# Pg06__SysBoot_LEDS_Mech.net
KiCad netlist of a schematic drawn in Altium Designer
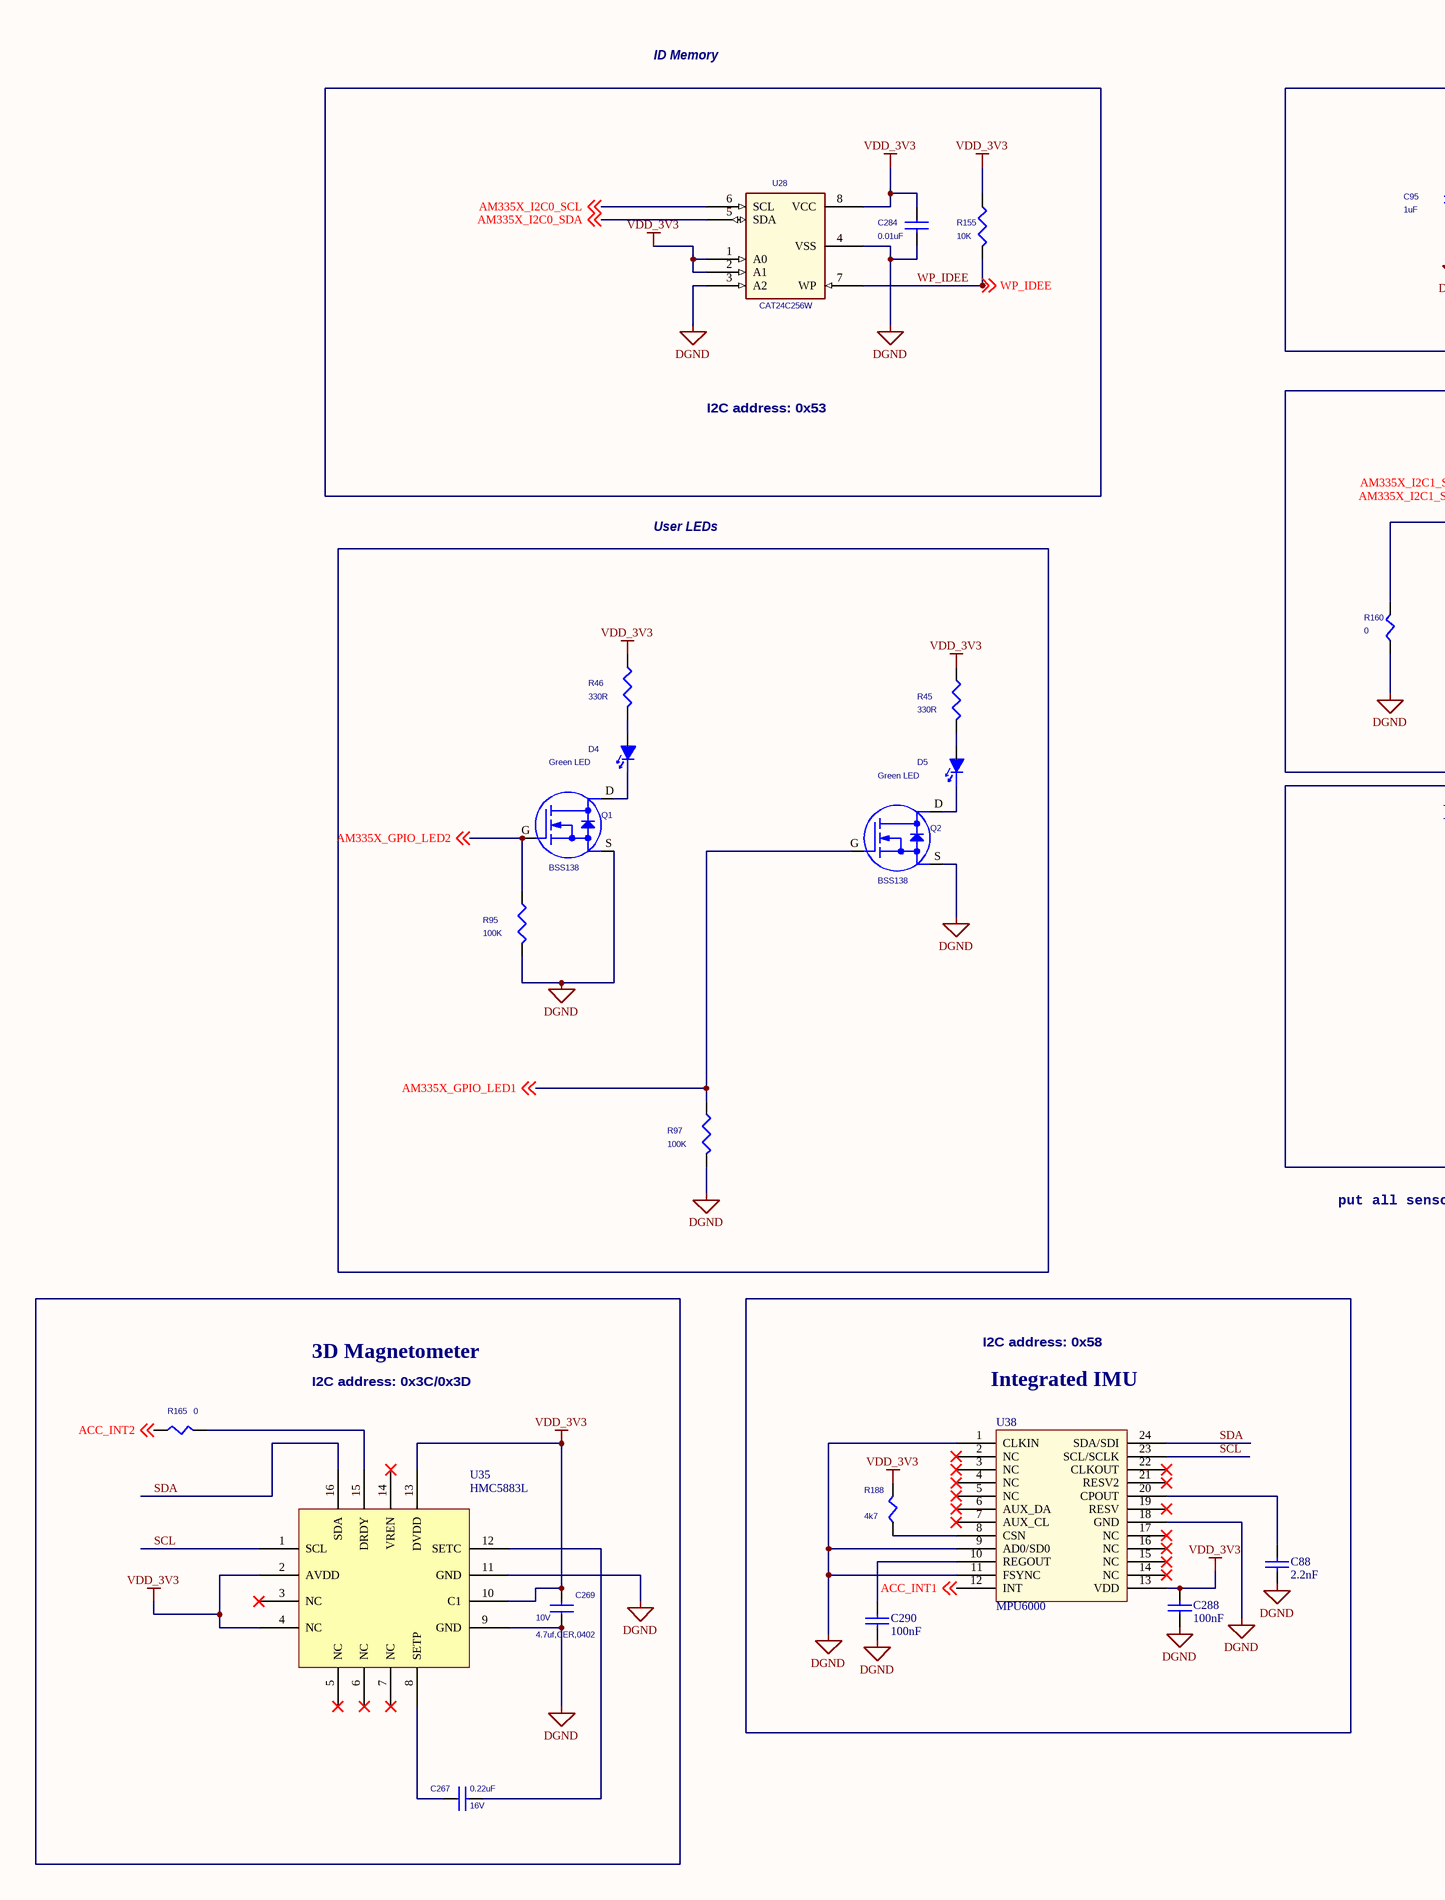
[diagram p0: Pg06_ SysBoot_LEDS_Mech.SchDoc, left]
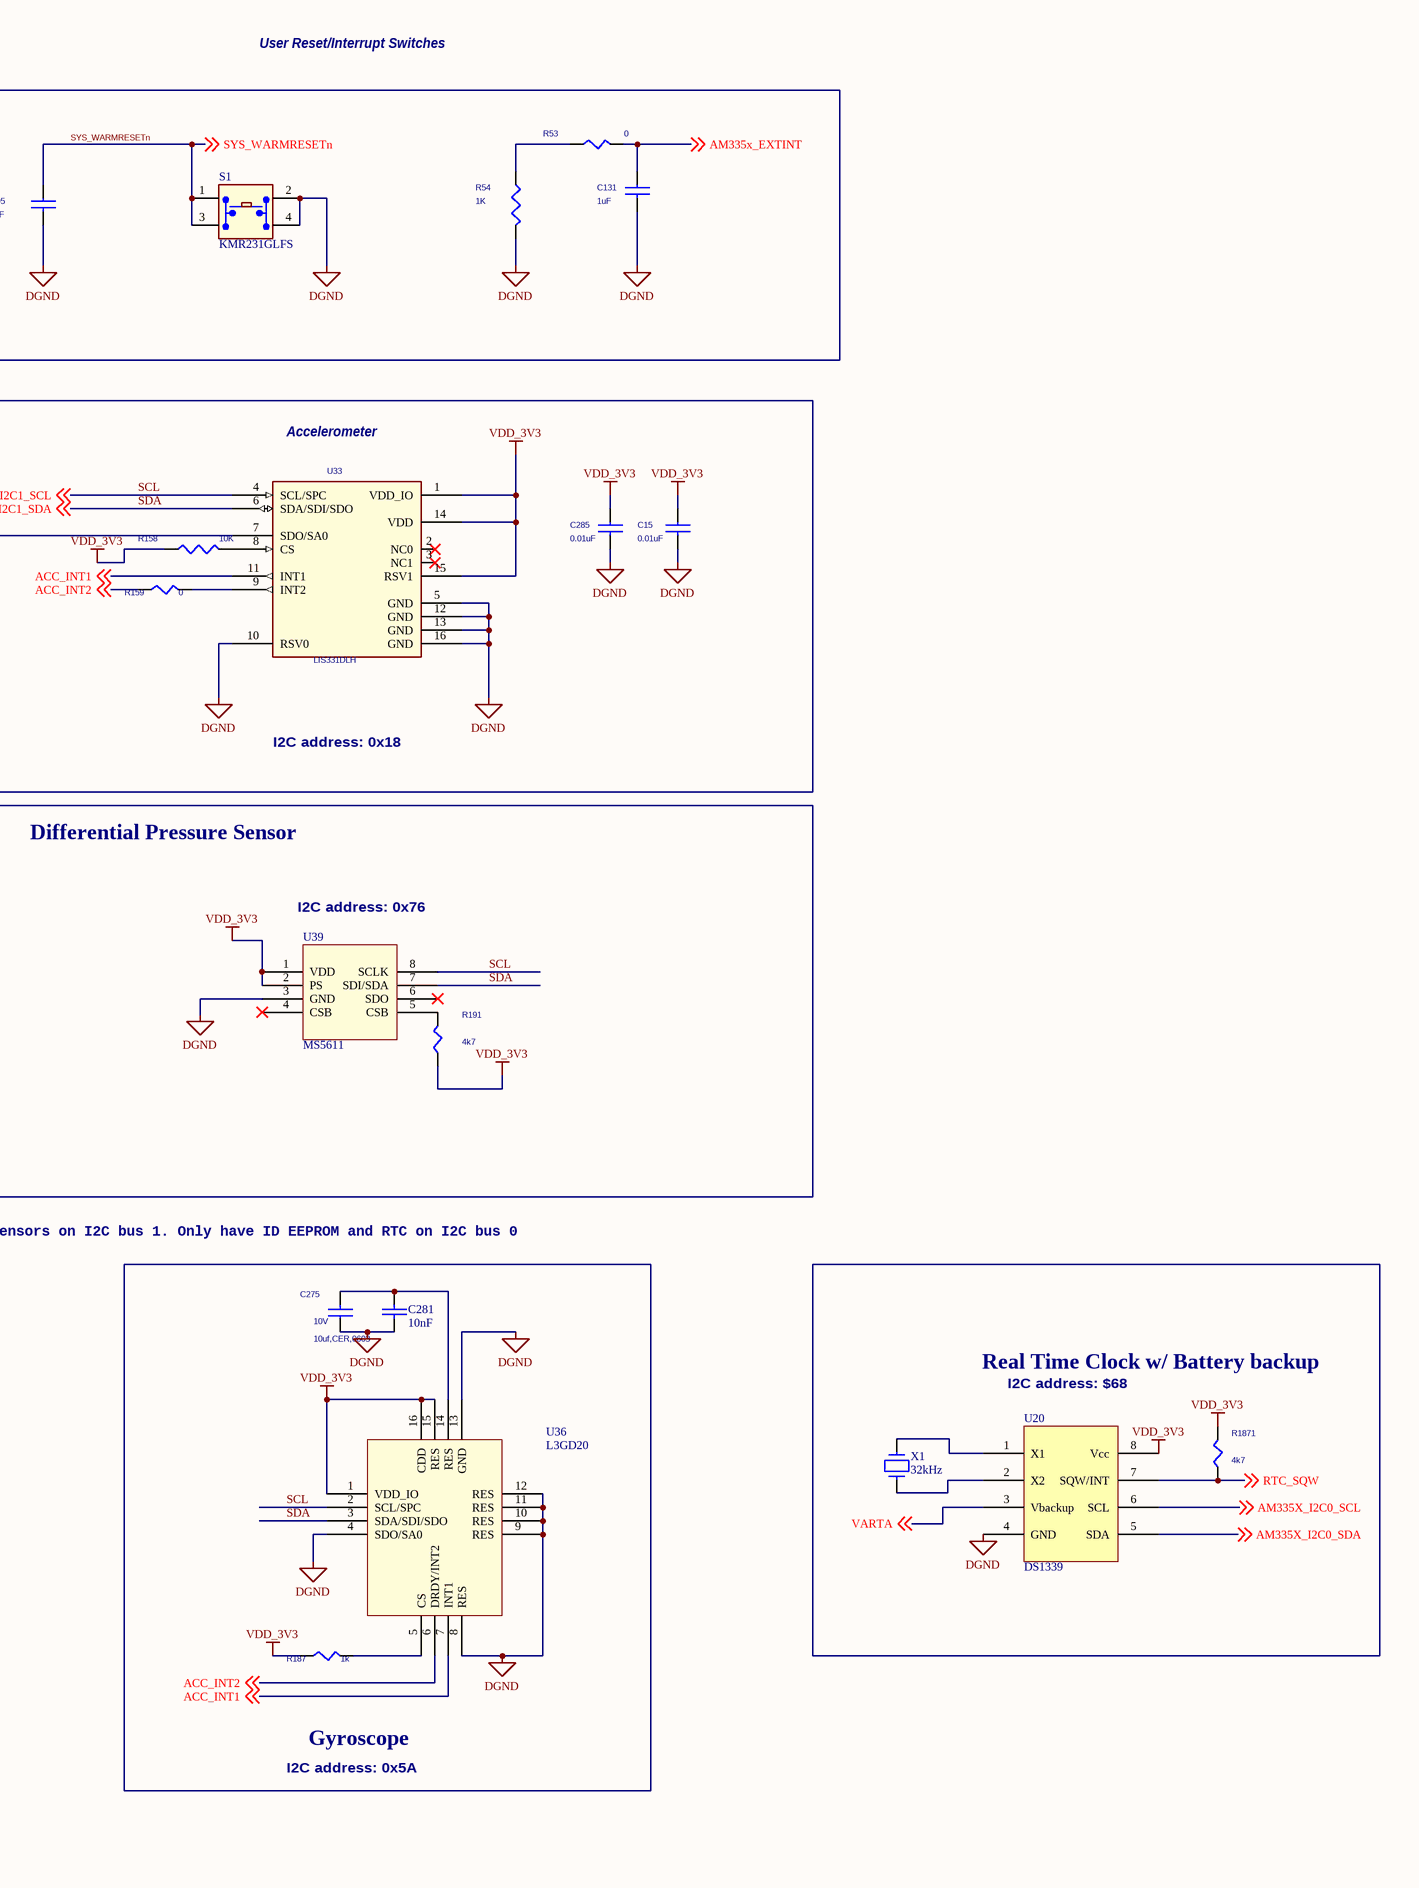
[diagram p1: Pg06_ SysBoot_LEDS_Mech.SchDoc, right]

(export (version "E")
  (design (tool "Eeschema 10.0.6"))
  (components
    (comp (ref "C15")
      (value "0.01uF")
      (footprint "SM-7351-CAP-0402")
      (fields (field (name "MFR") "Panasonic") (field (name "TIINTPARTNUMBER") "1C0012"))
      (libsource (lib "*") (part "0.01uFCapacitor16V10%0402_Dup1"))
    )
    (comp (ref "C88")
      (value "2.2nF")
      (footprint "0603")
      (description "Ceramic capacitor")
      (libsource (lib "CCDHeadBoard") (part "CAP_CER"))
    )
    (comp (ref "C95")
      (value "1uF")
      (footprint "SM-7351-CAP-0402")
      (fields (field (name "MFR") "AVX") (field (name "TIINTPARTNUMBER") "1C0084"))
      (libsource (lib "*") (part "1uFCapacitor10V10%0402_Dup1"))
    )
    (comp (ref "C131")
      (value "1uF")
      (footprint "SM-7351-CAP-0402")
      (fields (field (name "MFR") "AVX") (field (name "TIINTPARTNUMBER") "1C0084"))
      (libsource (lib "*") (part "1uFCapacitor10V10%0402_Dup1"))
    )
    (comp (ref "C267")
      (value "0.22uF")
      (footprint "sc0402")
      (fields (field (name "VOLTAGE") "16V"))
      (libsource (lib "*") (part "0402_0r01uf_x7r_16v_10"))
    )
    (comp (ref "C269")
      (value "4.7uf,CER,0402")
      (footprint "sc0402")
      (fields (field (name "VOLTAGE") "10V"))
      (libsource (lib "*") (part "cap_0402_0r1uf_x7r_10v"))
    )
    (comp (ref "C275")
      (value "10uf,CER,0603")
      (footprint "0603")
      (fields (field (name "VOLTAGE") "10V"))
      (libsource (lib "*") (part "cap_0402_0r1uf_x7r_10v"))
    )
    (comp (ref "C281")
      (value "10nF")
      (footprint "SM-7351-CAP-0402")
      (description "Ceramic capacitor")
      (libsource (lib "CCDHeadBoard") (part "CAP_CER"))
    )
    (comp (ref "C284")
      (value "0.01uF")
      (footprint "SM-7351-CAP-0402")
      (fields (field (name "MFR") "Panasonic") (field (name "TIINTPARTNUMBER") "1C0012"))
      (libsource (lib "*") (part "0.01uFCapacitor16V10%0402_Dup1"))
    )
    (comp (ref "C285")
      (value "0.01uF")
      (footprint "SM-7351-CAP-0402")
      (fields (field (name "MFR") "Panasonic") (field (name "TIINTPARTNUMBER") "1C0012"))
      (libsource (lib "*") (part "0.01uFCapacitor16V10%0402_Dup1"))
    )
    (comp (ref "C288")
      (value "100nF")
      (footprint "0603")
      (description "Ceramic capacitor")
      (libsource (lib "CCDHeadBoard") (part "CAP_CER"))
    )
    (comp (ref "C290")
      (value "100nF")
      (footprint "0603")
      (description "Ceramic capacitor")
      (libsource (lib "CCDHeadBoard") (part "CAP_CER"))
    )
    (comp (ref "D4")
      (value "Green LED")
      (footprint "sm_led_0805")
      (fields (field (name "TIINTPARTNUMBER") "1F0008") (field (name "MFR") "Dialight"))
      (libsource (lib "*") (part "LED_Green"))
    )
    (comp (ref "D5")
      (value "Green LED")
      (footprint "sm_led_0805")
      (fields (field (name "TIINTPARTNUMBER") "1F0008") (field (name "MFR") "Dialight"))
      (libsource (lib "*") (part "LED_Green"))
    )
    (comp (ref "Q1")
      (value "BSS138")
      (footprint "SOT23-3")
      (description "MOSFET Nchan 50V 200mA")
      (fields (field (name "TIINTPARTNUMBER") "1Q0019") (field (name "MFR") "Diodes Inc."))
      (libsource (lib "*") (part "MOSFET_NChan_BSS138_Dup1"))
    )
    (comp (ref "Q2")
      (value "BSS138")
      (footprint "SOT23-3")
      (description "MOSFET Nchan 50V 200mA")
      (fields (field (name "TIINTPARTNUMBER") "1Q0019") (field (name "MFR") "Diodes Inc."))
      (libsource (lib "*") (part "MOSFET_NChan_BSS138_Dup1"))
    )
    (comp (ref "R45")
      (value "330R")
      (footprint "SM-7351-RES-0402")
      (description "Resistor 150ohm 1/16W 5% 0402")
      (fields (field (name "MFR") "Stackpole Electronics") (field (name "TIINTPARTNUMBER") "1R0179"))
      (libsource (lib "*") (part "150ohm1/16W1%SMD0402"))
    )
    (comp (ref "R46")
      (value "330R")
      (footprint "SM-7351-RES-0402")
      (description "Resistor 150ohm 1/16W 5% 0402")
      (fields (field (name "MFR") "Stackpole Electronics") (field (name "TIINTPARTNUMBER") "1R0179"))
      (libsource (lib "*") (part "150ohm1/16W1%SMD0402"))
    )
    (comp (ref "R53")
      (value "0")
      (footprint "SM-7351-RES-0402")
      (description "Resistor Zero ohm Jumper 0402")
      (fields (field (name "TIINTPARTNUMBER") "1R0098") (field (name "MFR") "Panasonic"))
      (libsource (lib "*") (part "ZeroOhmResistor1/16W0402_Dup1"))
    )
    (comp (ref "R54")
      (value "1K")
      (footprint "SM-7351-RES-0402")
      (description "Resistor 1Kohm 1/16W 5% 0402")
      (fields (field (name "MFR") "Panasonic") (field (name "TIINTPARTNUMBER") "1R0027"))
      (libsource (lib "*") (part "1KOhmResistor1/16W0402_Dup1"))
    )
    (comp (ref "R95")
      (value "100K")
      (footprint "SM-7351-RES-0402")
      (fields (field (name "TIINTPARTNUMBER") "1R0181") (field (name "MFR") "Stackpole Electronics"))
      (libsource (lib "*") (part "100KOhmResistor1/16W0402_Dup1"))
    )
    (comp (ref "R97")
      (value "100K")
      (footprint "SM-7351-RES-0402")
      (fields (field (name "TIINTPARTNUMBER") "1R0181") (field (name "MFR") "Stackpole Electronics"))
      (libsource (lib "*") (part "100KOhmResistor1/16W0402_Dup1"))
    )
    (comp (ref "R155")
      (value "10K")
      (footprint "SM-7351-RES-0402")
      (description "Resistor 10Kohm 1/16W 5% 0402")
      (fields (field (name "TIINTPARTNUMBER") "1R0168") (field (name "MFR") "Rohm"))
      (libsource (lib "*") (part "10KOhmResistor1/16W0402_Dup1"))
    )
    (comp (ref "R158")
      (value "10K")
      (footprint "SM-7351-RES-0402")
      (description "Resistor 10Kohm 1/16W 5% 0402")
      (fields (field (name "TIINTPARTNUMBER") "1R0168") (field (name "MFR") "Rohm"))
      (libsource (lib "*") (part "10KOhmResistor1/16W0402_Dup1"))
    )
    (comp (ref "R159")
      (value "0")
      (footprint "SM-7351-RES-0402")
      (fields (field (name "MFR") "Panasonic") (field (name "TIINTPARTNUMBER") "1R0098"))
      (libsource (lib "*") (part "ZeroOhmResistor1/16W0402"))
    )
    (comp (ref "R160")
      (value "0")
      (footprint "SM-7351-RES-0402")
      (description "Resistor Zero ohm Jumper 0402")
      (fields (field (name "TIINTPARTNUMBER") "1R0098") (field (name "MFR") "Panasonic"))
      (libsource (lib "*") (part "ZeroOhmResistor1/16W0402_Dup4"))
    )
    (comp (ref "R165")
      (value "0")
      (footprint "SM-7351-RES-0402")
      (fields (field (name "MFR") "Panasonic") (field (name "TIINTPARTNUMBER") "1R0098"))
      (libsource (lib "*") (part "ZeroOhmResistor1/16W0402"))
    )
    (comp (ref "R187")
      (value "1k")
      (footprint "SM-7351-RES-0402")
      (fields (field (name "MFR") "Panasonic") (field (name "TIINTPARTNUMBER") "1R0098"))
      (libsource (lib "*") (part "ZeroOhmResistor1/16W0402"))
    )
    (comp (ref "R188")
      (value "4k7")
      (footprint "SM-7351-RES-0402")
      (fields (field (name "MFR") "Panasonic") (field (name "TIINTPARTNUMBER") "1R0098"))
      (libsource (lib "*") (part "ZeroOhmResistor1/16W0402"))
    )
    (comp (ref "R191")
      (value "4k7")
      (footprint "SM-7351-RES-0402")
      (fields (field (name "MFR") "Panasonic") (field (name "TIINTPARTNUMBER") "1R0098"))
      (libsource (lib "*") (part "ZeroOhmResistor1/16W0402"))
    )
    (comp (ref "R1871")
      (value "4k7")
      (footprint "SM-7351-RES-0402")
      (fields (field (name "MFR") "Panasonic") (field (name "TIINTPARTNUMBER") "1R0098"))
      (libsource (lib "*") (part "ZeroOhmResistor1/16W0402"))
    )
    (comp (ref "S1")
      (value "KMR231GLFS")
      (footprint "SW4SMD_63X161LS")
      (description "Microminiature Tact Switch for SMT")
      (fields (field (name "MANUFACTURER") "C&K Components"))
      (libsource (lib "BEAGLEBONEBLACK_REV A5B") (part "KMR2"))
    )
    (comp (ref "U20")
      (value "DS1339")
      (footprint "MSOP-MS8_N")
      (description "DS1339 RTC")
      (libsource (lib "Fireflash_B") (part "DS1339"))
    )
    (comp (ref "U28")
      (value "CAT24C256W")
      (footprint "SOIC_8")
      (description "EEPROM 256Kb I2C SOIC8")
      (fields (field (name "TIINTPARTNUMBER") "1A0225") (field (name "MFR") "On Semiconductor"))
      (libsource (lib "*") (part "CAT24C256W"))
    )
    (comp (ref "U33")
      (value "LIS331DLH")
      (footprint "LGA16pin_3x3")
      (description "Accelerometer 3 Axis I2C")
      (fields (field (name "MFR") "ST Microelectronics") (field (name "TIINTPARTNUMBER") "1A0227"))
      (libsource (lib "*") (part "LIS331DLH"))
    )
    (comp (ref "U35")
      (value "HMC5883L")
      (footprint "LPCC package")
      (description "3D Magnetometer")
      (libsource (lib "Fireflash_B") (part "HMC5883L"))
    )
    (comp (ref "U36")
      (value "L3GD20")
      (footprint "LCC 16pin 4x4mm 0.65mm pitch")
      (libsource (lib "testlib") (part "L3GD20"))
    )
    (comp (ref "U38")
      (value "MPU6000")
      (footprint "QFN_EPAD_24")
      (description "Invensemse 6-axis MPU")
      (libsource (lib "RedCape") (part "IMU6000"))
    )
    (comp (ref "U39")
      (value "MS5611")
      (footprint "MS5611-01BA03")
      (description "Pressure Sensor")
      (libsource (lib "RedCape") (part "MS5611"))
    )
    (comp (ref "X1")
      (value "32kHz")
      (footprint "Xtal 3215")
      (description "CRYSTAL")
      (libsource (lib "Fireflash_B") (part "CRYSTAL"))
    )
  )
  (nets
    (net (code "1") (name "ACC_INT1") (class "Default")
      (node (ref "U33") (pin "11") (pinfunction "INT1_11") (pintype "output"))
      (node (ref "U36") (pin "7") (pinfunction "INT1_7") (pintype "passive"))
      (node (ref "U38") (pin "12") (pinfunction "INT_12") (pintype "passive"))
    )
    (net (code "2") (name "ACC_INT2") (class "Default")
      (node (ref "R159") (pin "2") (pinfunction "P2_2") (pintype "passive"))
      (node (ref "R165") (pin "2") (pinfunction "P2_2") (pintype "passive"))
      (node (ref "U36") (pin "6") (pinfunction "DRDY/INT2_6") (pintype "passive"))
    )
    (net (code "3") (name "AM335X_GPIO_LED1") (class "Default")
      (node (ref "Q2") (pin "G") (pinfunction "GATE_G") (pintype "passive"))
      (node (ref "R97") (pin "2") (pinfunction "P2_2") (pintype "passive"))
    )
    (net (code "4") (name "AM335X_GPIO_LED2") (class "Default")
      (node (ref "Q1") (pin "G") (pinfunction "GATE_G") (pintype "passive"))
      (node (ref "R95") (pin "2") (pinfunction "P2_2") (pintype "passive"))
    )
    (net (code "5") (name "AM335X_I2C0_SCL") (class "Default")
      (node (ref "U20") (pin "6") (pinfunction "SCL_6") (pintype "passive"))
      (node (ref "U28") (pin "6") (pinfunction "SCL_6") (pintype "input"))
    )
    (net (code "6") (name "AM335X_I2C0_SDA") (class "Default")
      (node (ref "U20") (pin "5") (pinfunction "SDA_5") (pintype "passive"))
      (node (ref "U28") (pin "5") (pinfunction "SDA_5") (pintype "bidirectional"))
    )
    (net (code "7") (name "AM335X_I2C1_SCL") (class "Default")
      (node (ref "U33") (pin "4") (pinfunction "SCL/SPC_4") (pintype "input"))
      (node (ref "U35") (pin "1") (pinfunction "SCL_1") (pintype "passive"))
      (node (ref "U36") (pin "2") (pinfunction "SCL/SPC_2") (pintype "passive"))
      (node (ref "U38") (pin "23") (pinfunction "SCL/SCLK_23") (pintype "passive"))
      (node (ref "U39") (pin "8") (pinfunction "SCLK_8") (pintype "passive"))
    )
    (net (code "8") (name "AM335X_I2C1_SDA") (class "Default")
      (node (ref "U33") (pin "6") (pinfunction "SDA/SDI/SDO_6") (pintype "bidirectional"))
      (node (ref "U35") (pin "16") (pinfunction "SDA_16") (pintype "passive"))
      (node (ref "U36") (pin "3") (pinfunction "SDA/SDI/SDO_3") (pintype "passive"))
      (node (ref "U38") (pin "24") (pinfunction "SDA/SDI_24") (pintype "passive"))
      (node (ref "U39") (pin "7") (pinfunction "SDI/SDA_7") (pintype "passive"))
    )
    (net (code "9") (name "AM335x_EXTINT") (class "Default")
      (node (ref "C131") (pin "1") (pinfunction "1_1") (pintype "passive"))
      (node (ref "R53") (pin "1") (pinfunction "P1_1") (pintype "passive"))
    )
    (net (code "10") (name "DGND") (class "Default")
      (node (ref "C131") (pin "2") (pinfunction "2_2") (pintype "passive"))
      (node (ref "C15") (pin "2") (pinfunction "2_2") (pintype "passive"))
      (node (ref "C269") (pin "1") (pinfunction "1_1") (pintype "passive"))
      (node (ref "C275") (pin "1") (pinfunction "1_1") (pintype "passive"))
      (node (ref "C281") (pin "2") (pintype "passive"))
      (node (ref "C284") (pin "2") (pinfunction "2_2") (pintype "passive"))
      (node (ref "C285") (pin "2") (pinfunction "2_2") (pintype "passive"))
      (node (ref "C288") (pin "2") (pintype "passive"))
      (node (ref "C290") (pin "2") (pintype "passive"))
      (node (ref "C88") (pin "2") (pintype "passive"))
      (node (ref "C95") (pin "2") (pinfunction "2_2") (pintype "passive"))
      (node (ref "Q1") (pin "S") (pinfunction "SOURCE_S") (pintype "passive"))
      (node (ref "Q2") (pin "S") (pinfunction "SOURCE_S") (pintype "passive"))
      (node (ref "R160") (pin "2") (pinfunction "P2_2") (pintype "passive"))
      (node (ref "R54") (pin "1") (pinfunction "P1_1") (pintype "passive"))
      (node (ref "R95") (pin "1") (pinfunction "P1_1") (pintype "passive"))
      (node (ref "R97") (pin "1") (pinfunction "P1_1") (pintype "passive"))
      (node (ref "S1") (pin "2") (pinfunction "A2_2") (pintype "passive"))
      (node (ref "S1") (pin "4") (pinfunction "4_4") (pintype "power_in"))
      (node (ref "U20") (pin "4") (pinfunction "GND_4") (pintype "passive"))
      (node (ref "U28") (pin "3") (pinfunction "A2_3") (pintype "input"))
      (node (ref "U28") (pin "4") (pinfunction "VSS_4") (pintype "power_in"))
      (node (ref "U33") (pin "10") (pinfunction "RSV0_10") (pintype "passive"))
      (node (ref "U33") (pin "12") (pinfunction "GND_12") (pintype "power_in"))
      (node (ref "U33") (pin "13") (pinfunction "GND_13") (pintype "power_in"))
      (node (ref "U33") (pin "16") (pinfunction "GND_16") (pintype "power_in"))
      (node (ref "U33") (pin "5") (pinfunction "GND_5") (pintype "power_in"))
      (node (ref "U35") (pin "11") (pinfunction "GND_11") (pintype "passive"))
      (node (ref "U35") (pin "9") (pinfunction "GND_9") (pintype "passive"))
      (node (ref "U36") (pin "10") (pinfunction "RES_10") (pintype "passive"))
      (node (ref "U36") (pin "11") (pinfunction "RES_11") (pintype "passive"))
      (node (ref "U36") (pin "12") (pinfunction "RES_12") (pintype "passive"))
      (node (ref "U36") (pin "13") (pinfunction "GND_13") (pintype "passive"))
      (node (ref "U36") (pin "4") (pinfunction "SDO/SA0_4") (pintype "passive"))
      (node (ref "U36") (pin "8") (pinfunction "RES_8") (pintype "passive"))
      (node (ref "U36") (pin "9") (pinfunction "RES_9") (pintype "passive"))
      (node (ref "U38") (pin "1") (pinfunction "CLKIN_1") (pintype "passive"))
      (node (ref "U38") (pin "11") (pinfunction "FSYNC_11") (pintype "passive"))
      (node (ref "U38") (pin "18") (pinfunction "GND_18") (pintype "passive"))
      (node (ref "U38") (pin "9") (pinfunction "AD0/SD0_9") (pintype "passive"))
      (node (ref "U39") (pin "3") (pinfunction "GND_3") (pintype "passive"))
    )
    (net (code "11") (name "Net-(C275-Pad2)") (class "Default")
      (node (ref "C275") (pin "2") (pinfunction "2_2") (pintype "passive"))
      (node (ref "C281") (pin "1") (pintype "passive"))
      (node (ref "U36") (pin "14") (pinfunction "RES_14") (pintype "passive"))
    )
    (net (code "12") (name "Net-(D4-Anode)") (class "Default")
      (node (ref "D4") (pin "2") (pinfunction "Anode_2") (pintype "passive"))
      (node (ref "R46") (pin "1") (pinfunction "P1_1") (pintype "passive"))
    )
    (net (code "13") (name "Net-(D4-Cathode)") (class "Default")
      (node (ref "D4") (pin "1") (pinfunction "Cathode_1") (pintype "passive"))
      (node (ref "Q1") (pin "D") (pinfunction "DRAIN_D") (pintype "passive"))
    )
    (net (code "14") (name "Net-(D5-Anode)") (class "Default")
      (node (ref "D5") (pin "2") (pinfunction "Anode_2") (pintype "passive"))
      (node (ref "R45") (pin "1") (pinfunction "P1_1") (pintype "passive"))
    )
    (net (code "15") (name "Net-(D5-Cathode)") (class "Default")
      (node (ref "D5") (pin "1") (pinfunction "Cathode_1") (pintype "passive"))
      (node (ref "Q2") (pin "D") (pinfunction "DRAIN_D") (pintype "passive"))
    )
    (net (code "16") (name "Net-(R53-P2)") (class "Default")
      (node (ref "R53") (pin "2") (pinfunction "P2_2") (pintype "passive"))
      (node (ref "R54") (pin "2") (pinfunction "P2_2") (pintype "passive"))
    )
    (net (code "17") (name "Net-(R158-P1)") (class "Default")
      (node (ref "R158") (pin "1") (pinfunction "P1_1") (pintype "passive"))
      (node (ref "U33") (pin "8") (pinfunction "CS_8") (pintype "input"))
    )
    (net (code "18") (name "Net-(R159-P1)") (class "Default")
      (node (ref "R159") (pin "1") (pinfunction "P1_1") (pintype "passive"))
      (node (ref "U33") (pin "9") (pinfunction "INT2_9") (pintype "output"))
    )
    (net (code "19") (name "Net-(R160-P1)") (class "Default")
      (node (ref "R160") (pin "1") (pinfunction "P1_1") (pintype "passive"))
      (node (ref "U33") (pin "7") (pinfunction "SDO/SA0_7") (pintype "passive"))
    )
    (net (code "20") (name "Net-(R165-P1)") (class "Default")
      (node (ref "R165") (pin "1") (pinfunction "P1_1") (pintype "passive"))
      (node (ref "U35") (pin "15") (pinfunction "DRDY_15") (pintype "passive"))
    )
    (net (code "21") (name "Net-(R187-P1)") (class "Default")
      (node (ref "R187") (pin "1") (pinfunction "P1_1") (pintype "passive"))
      (node (ref "U36") (pin "5") (pinfunction "CS_5") (pintype "passive"))
    )
    (net (code "22") (name "Net-(R188-P2)") (class "Default")
      (node (ref "R188") (pin "2") (pinfunction "P2_2") (pintype "passive"))
      (node (ref "U38") (pin "8") (pinfunction "CSN_8") (pintype "passive"))
    )
    (net (code "23") (name "Net-(R191-P1)") (class "Default")
      (node (ref "R191") (pin "1") (pinfunction "P1_1") (pintype "passive"))
      (node (ref "U39") (pin "5") (pinfunction "CSB_5") (pintype "passive"))
    )
    (net (code "24") (name "Net-(U20-X1)") (class "Default")
      (node (ref "U20") (pin "1") (pinfunction "X1_1") (pintype "passive"))
      (node (ref "X1") (pin "2") (pintype "passive"))
    )
    (net (code "25") (name "Net-(U20-X2)") (class "Default")
      (node (ref "U20") (pin "2") (pinfunction "X2_2") (pintype "passive"))
      (node (ref "X1") (pin "1") (pintype "passive"))
    )
    (net (code "26") (name "Net-(U35-SETC)") (class "Default")
      (node (ref "C267") (pin "2") (pinfunction "2_2") (pintype "passive"))
      (node (ref "U35") (pin "12") (pinfunction "SETC_12") (pintype "passive"))
    )
    (net (code "27") (name "Net-(U35-SETP)") (class "Default")
      (node (ref "C267") (pin "1") (pinfunction "1_1") (pintype "passive"))
      (node (ref "U35") (pin "8") (pinfunction "SETP_8") (pintype "passive"))
    )
    (net (code "28") (name "Net-(U38-CPOUT)") (class "Default")
      (node (ref "C88") (pin "1") (pintype "passive"))
      (node (ref "U38") (pin "20") (pinfunction "CPOUT_20") (pintype "passive"))
    )
    (net (code "29") (name "Net-(U38-REGOUT)") (class "Default")
      (node (ref "C290") (pin "1") (pintype "passive"))
      (node (ref "U38") (pin "10") (pinfunction "REGOUT_10") (pintype "passive"))
    )
    (net (code "30") (name "RTC_SQW") (class "Default")
      (node (ref "R1871") (pin "2") (pinfunction "P2_2") (pintype "passive"))
      (node (ref "U20") (pin "7") (pinfunction "SQW/INT_7") (pintype "passive"))
    )
    (net (code "31") (name "SYS_WARMRESETn") (class "Default")
      (node (ref "C95") (pin "1") (pinfunction "1_1") (pintype "passive"))
      (node (ref "S1") (pin "1") (pinfunction "A1_1") (pintype "passive"))
      (node (ref "S1") (pin "3") (pinfunction "A3_3") (pintype "passive"))
    )
    (net (code "32") (name "VARTA") (class "Default")
      (node (ref "U20") (pin "3") (pinfunction "Vbackup_3") (pintype "passive"))
    )
    (net (code "33") (name "VDD_3V3") (class "Default")
      (node (ref "C15") (pin "1") (pinfunction "1_1") (pintype "passive"))
      (node (ref "C269") (pin "2") (pinfunction "2_2") (pintype "passive"))
      (node (ref "C284") (pin "1") (pinfunction "1_1") (pintype "passive"))
      (node (ref "C285") (pin "1") (pinfunction "1_1") (pintype "passive"))
      (node (ref "C288") (pin "1") (pintype "passive"))
      (node (ref "R155") (pin "2") (pinfunction "P2_2") (pintype "passive"))
      (node (ref "R158") (pin "2") (pinfunction "P2_2") (pintype "passive"))
      (node (ref "R187") (pin "2") (pinfunction "P2_2") (pintype "passive"))
      (node (ref "R1871") (pin "1") (pinfunction "P1_1") (pintype "passive"))
      (node (ref "R188") (pin "1") (pinfunction "P1_1") (pintype "passive"))
      (node (ref "R191") (pin "2") (pinfunction "P2_2") (pintype "passive"))
      (node (ref "R45") (pin "2") (pinfunction "P2_2") (pintype "passive"))
      (node (ref "R46") (pin "2") (pinfunction "P2_2") (pintype "passive"))
      (node (ref "U20") (pin "8") (pinfunction "Vcc_8") (pintype "passive"))
      (node (ref "U28") (pin "1") (pinfunction "A0_1") (pintype "input"))
      (node (ref "U28") (pin "2") (pinfunction "A1_2") (pintype "input"))
      (node (ref "U28") (pin "8") (pinfunction "VCC_8") (pintype "power_in"))
      (node (ref "U33") (pin "1") (pinfunction "VDD_IO_1") (pintype "power_in"))
      (node (ref "U33") (pin "14") (pinfunction "VDD_14") (pintype "power_in"))
      (node (ref "U33") (pin "15") (pinfunction "RSV1_15") (pintype "passive"))
      (node (ref "U35") (pin "10") (pinfunction "C1_10") (pintype "passive"))
      (node (ref "U35") (pin "13") (pinfunction "DVDD_13") (pintype "passive"))
      (node (ref "U35") (pin "2") (pinfunction "AVDD_2") (pintype "passive"))
      (node (ref "U35") (pin "4") (pinfunction "NC_4") (pintype "passive"))
      (node (ref "U36") (pin "1") (pinfunction "VDD_IO_1") (pintype "passive"))
      (node (ref "U36") (pin "15") (pinfunction "RES_15") (pintype "passive"))
      (node (ref "U36") (pin "16") (pinfunction "CDD_16") (pintype "passive"))
      (node (ref "U38") (pin "13") (pinfunction "VDD_13") (pintype "passive"))
      (node (ref "U39") (pin "1") (pinfunction "VDD_1") (pintype "passive"))
      (node (ref "U39") (pin "2") (pinfunction "PS_2") (pintype "passive"))
    )
    (net (code "34") (name "WP_IDEE") (class "Default")
      (node (ref "R155") (pin "1") (pinfunction "P1_1") (pintype "passive"))
      (node (ref "U28") (pin "7") (pinfunction "WP_7") (pintype "input"))
    )
    (net (code "35") (name "unconnected-(U33-NC0-Pad2)") (class "Default")
      (node (ref "U33") (pin "2") (pinfunction "NC0_2") (pintype "power_in+no_connect"))
    )
    (net (code "36") (name "unconnected-(U33-NC1-Pad3)") (class "Default")
      (node (ref "U33") (pin "3") (pinfunction "NC1_3") (pintype "power_in+no_connect"))
    )
    (net (code "37") (name "unconnected-(U35-NC-Pad3)") (class "Default")
      (node (ref "U35") (pin "3") (pinfunction "NC_3") (pintype "passive+no_connect"))
    )
    (net (code "38") (name "unconnected-(U35-NC-Pad5)") (class "Default")
      (node (ref "U35") (pin "5") (pinfunction "NC_5") (pintype "passive+no_connect"))
    )
    (net (code "39") (name "unconnected-(U35-NC-Pad6)") (class "Default")
      (node (ref "U35") (pin "6") (pinfunction "NC_6") (pintype "passive+no_connect"))
    )
    (net (code "40") (name "unconnected-(U35-NC-Pad7)") (class "Default")
      (node (ref "U35") (pin "7") (pinfunction "NC_7") (pintype "passive+no_connect"))
    )
    (net (code "41") (name "unconnected-(U35-VREN-Pad14)") (class "Default")
      (node (ref "U35") (pin "14") (pinfunction "VREN_14") (pintype "passive+no_connect"))
    )
    (net (code "42") (name "unconnected-(U38-AUX_CL-Pad7)") (class "Default")
      (node (ref "U38") (pin "7") (pinfunction "AUX_CL_7") (pintype "passive+no_connect"))
    )
    (net (code "43") (name "unconnected-(U38-AUX_DA-Pad6)") (class "Default")
      (node (ref "U38") (pin "6") (pinfunction "AUX_DA_6") (pintype "passive+no_connect"))
    )
    (net (code "44") (name "unconnected-(U38-CLKOUT-Pad22)") (class "Default")
      (node (ref "U38") (pin "22") (pinfunction "CLKOUT_22") (pintype "passive+no_connect"))
    )
    (net (code "45") (name "unconnected-(U38-NC-Pad2)") (class "Default")
      (node (ref "U38") (pin "2") (pinfunction "NC_2") (pintype "passive+no_connect"))
    )
    (net (code "46") (name "unconnected-(U38-NC-Pad3)") (class "Default")
      (node (ref "U38") (pin "3") (pinfunction "NC_3") (pintype "passive+no_connect"))
    )
    (net (code "47") (name "unconnected-(U38-NC-Pad4)") (class "Default")
      (node (ref "U38") (pin "4") (pinfunction "NC_4") (pintype "passive+no_connect"))
    )
    (net (code "48") (name "unconnected-(U38-NC-Pad5)") (class "Default")
      (node (ref "U38") (pin "5") (pinfunction "NC_5") (pintype "passive+no_connect"))
    )
    (net (code "49") (name "unconnected-(U38-NC-Pad14)") (class "Default")
      (node (ref "U38") (pin "14") (pinfunction "NC_14") (pintype "passive+no_connect"))
    )
    (net (code "50") (name "unconnected-(U38-NC-Pad15)") (class "Default")
      (node (ref "U38") (pin "15") (pinfunction "NC_15") (pintype "passive+no_connect"))
    )
    (net (code "51") (name "unconnected-(U38-NC-Pad16)") (class "Default")
      (node (ref "U38") (pin "16") (pinfunction "NC_16") (pintype "passive+no_connect"))
    )
    (net (code "52") (name "unconnected-(U38-NC-Pad17)") (class "Default")
      (node (ref "U38") (pin "17") (pinfunction "NC_17") (pintype "passive+no_connect"))
    )
    (net (code "53") (name "unconnected-(U38-RESV-Pad19)") (class "Default")
      (node (ref "U38") (pin "19") (pinfunction "RESV_19") (pintype "passive+no_connect"))
    )
    (net (code "54") (name "unconnected-(U38-RESV2-Pad21)") (class "Default")
      (node (ref "U38") (pin "21") (pinfunction "RESV2_21") (pintype "passive+no_connect"))
    )
    (net (code "55") (name "unconnected-(U39-CSB-Pad4)") (class "Default")
      (node (ref "U39") (pin "4") (pinfunction "CSB_4") (pintype "passive+no_connect"))
    )
    (net (code "56") (name "unconnected-(U39-SDO-Pad6)") (class "Default")
      (node (ref "U39") (pin "6") (pinfunction "SDO_6") (pintype "passive+no_connect"))
    )
  )
)
